# Mando.net
KiCad netlist of a schematic drawn in EAGLE
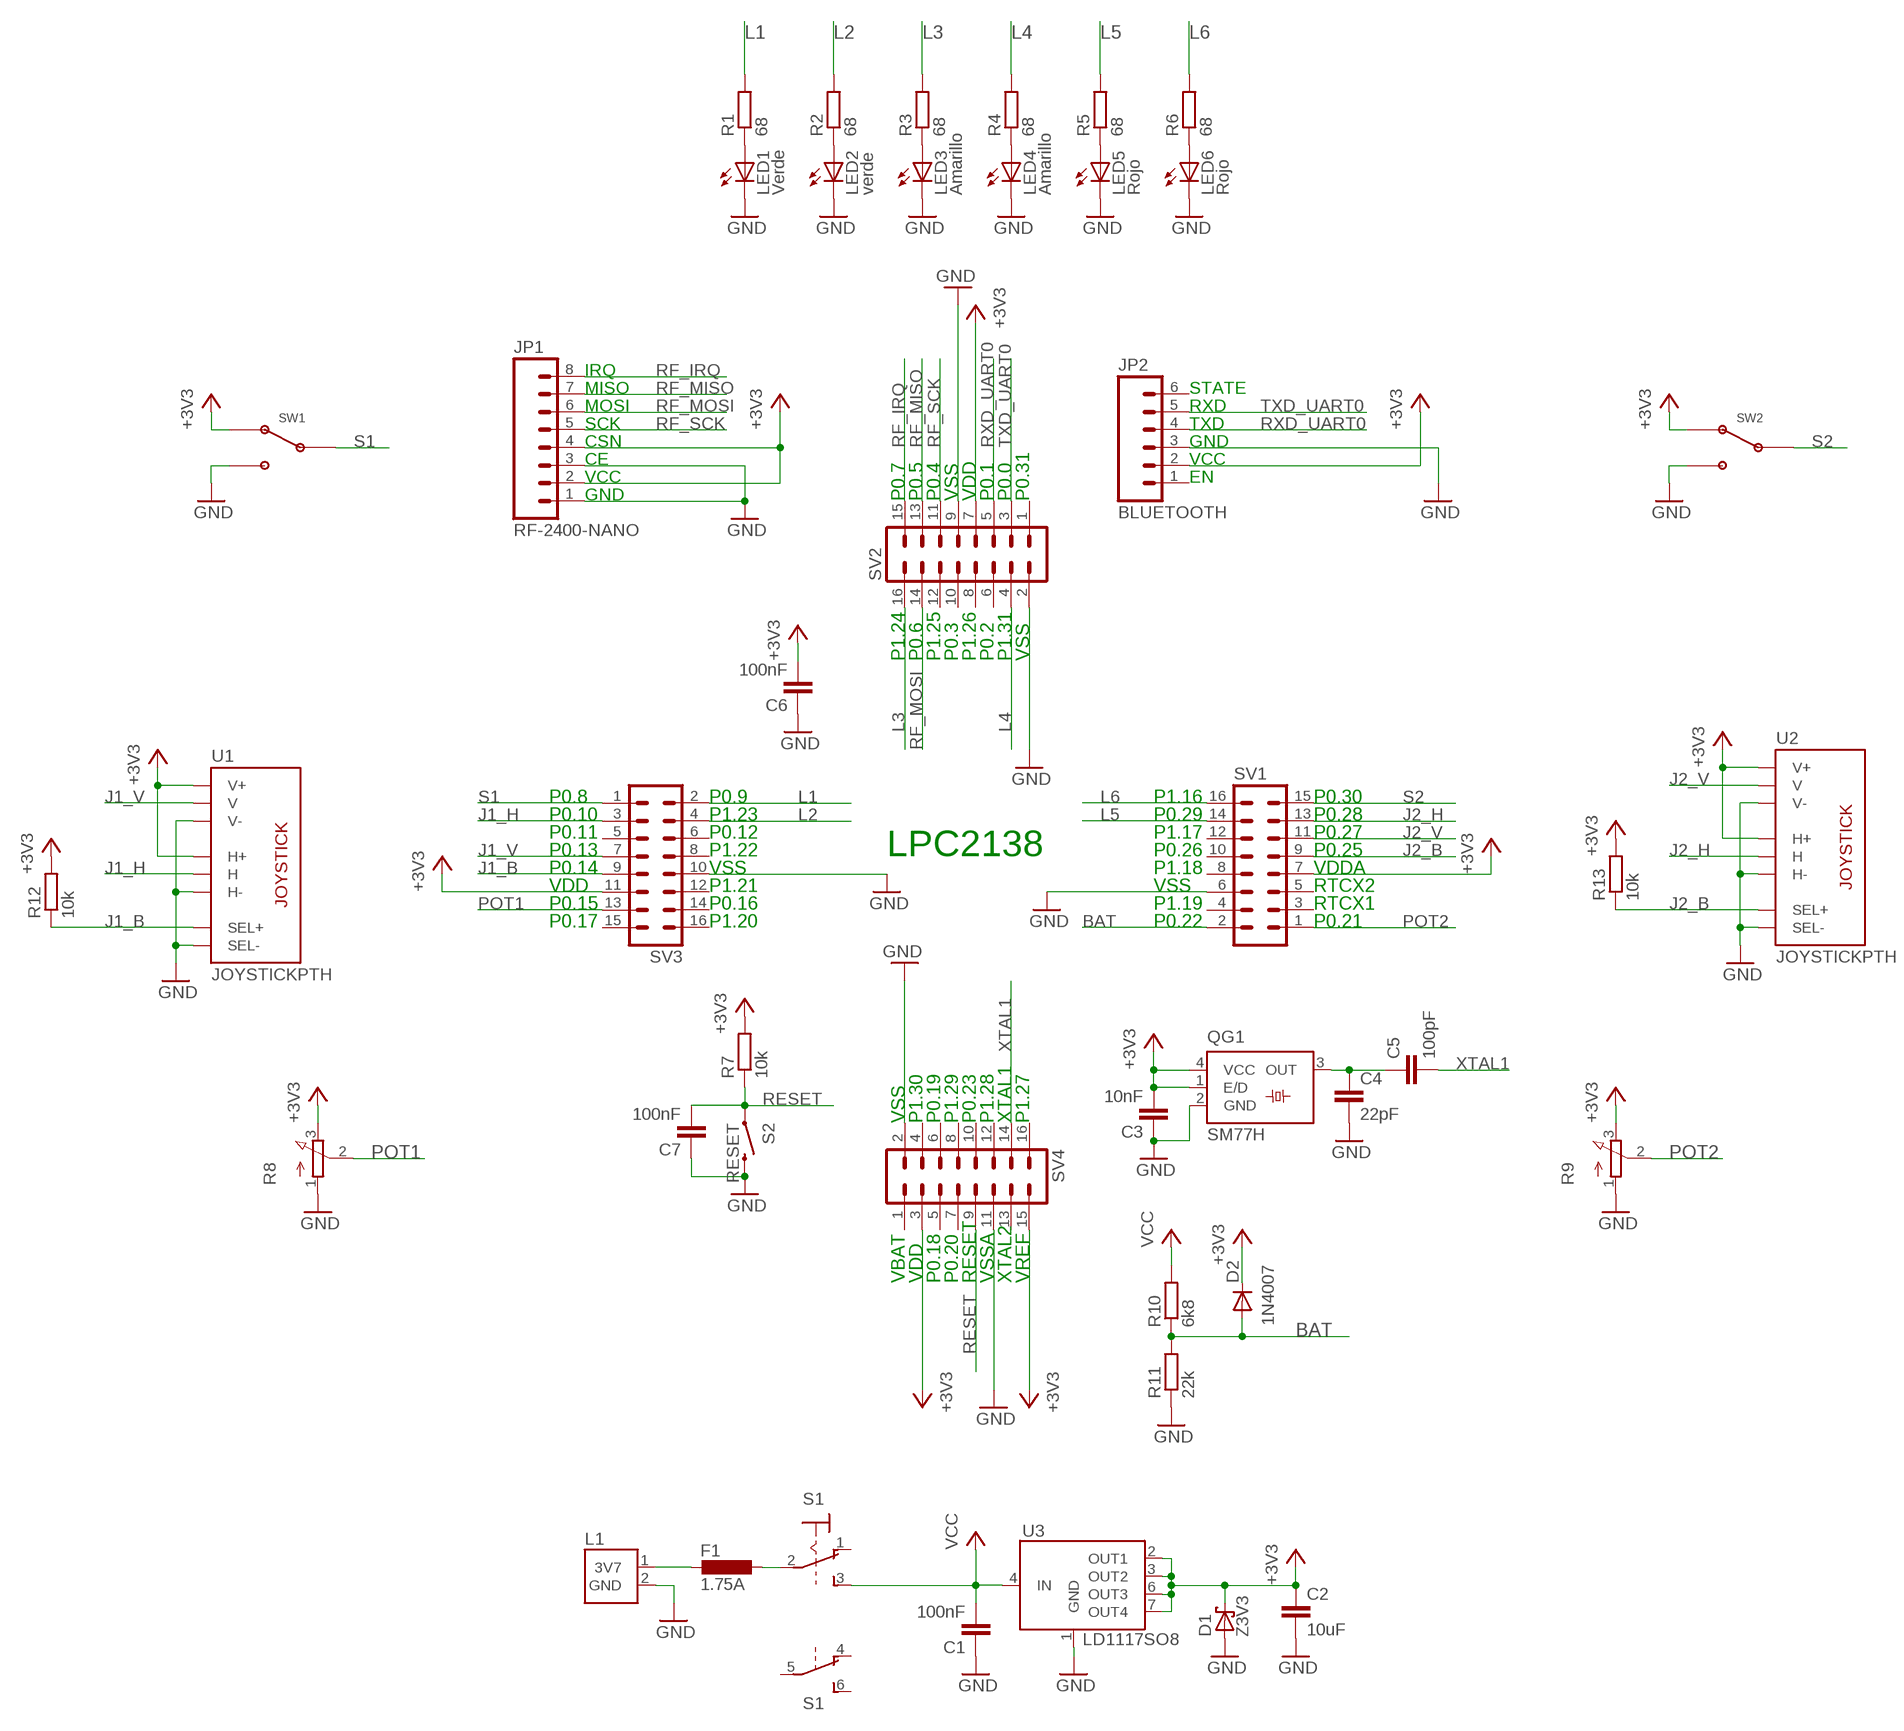
[diagram p0: schematic, sheet 1]

(export (version "E")
  (design (tool "Eeschema 10.0.6"))
  (components
    (comp (ref "C1")
      (value "100nF")
      (footprint "eagle-import:C0805")
      (libsource (lib "eagle-import") (part "C-EUC0805"))
    )
    (comp (ref "C2")
      (value "10uF")
      (footprint "eagle-import:C1206")
      (libsource (lib "eagle-import") (part "C-EUC1206"))
    )
    (comp (ref "C3")
      (value "10nF")
      (footprint "eagle-import:C0805")
      (libsource (lib "eagle-import") (part "C-EUC0805"))
    )
    (comp (ref "C4")
      (value "22pF")
      (footprint "eagle-import:C0805")
      (libsource (lib "eagle-import") (part "C-EUC0805"))
    )
    (comp (ref "C5")
      (value "100pF")
      (footprint "eagle-import:C0805")
      (libsource (lib "eagle-import") (part "C-EUC0805"))
    )
    (comp (ref "C6")
      (value "100nF")
      (footprint "eagle-import:C0805")
      (libsource (lib "eagle-import") (part "C-EUC0805"))
    )
    (comp (ref "C7")
      (value "100nF")
      (footprint "eagle-import:C0805")
      (libsource (lib "eagle-import") (part "C-EUC0805"))
    )
    (comp (ref "D1")
      (value "Z3V3")
      (footprint "eagle-import:DO35-7")
      (libsource (lib "eagle-import") (part "SCHOTTKY-DIODEDO35-7"))
    )
    (comp (ref "D2")
      (value "1N4007")
      (footprint "eagle-import:SOD106-R")
      (libsource (lib "eagle-import") (part "DIODE-SOD106-R"))
    )
    (comp (ref "F1")
      (value "1.75A")
      (footprint "eagle-import:L1812")
      (libsource (lib "eagle-import") (part "L-EUL1812"))
    )
    (comp (ref "JP1")
      (value "RF-2400-NANO")
      (footprint "eagle-import:1X08")
      (libsource (lib "eagle-import") (part "M081X08"))
    )
    (comp (ref "JP2")
      (value "BLUETOOTH")
      (footprint "eagle-import:1X06")
      (libsource (lib "eagle-import") (part "M06SIP"))
    )
    (comp (ref "L1")
      (value "CONECTOR_LIPO_3.7V")
      (footprint "eagle-import:CONECTOR_LIPO_3.7V")
      (libsource (lib "eagle-import") (part "CONECTOR_LIPO_3.7V"))
    )
    (comp (ref "LED1")
      (value "Verde")
      (footprint "eagle-import:LED3MM")
      (libsource (lib "eagle-import") (part "LED3MM"))
    )
    (comp (ref "LED2")
      (value "verde")
      (footprint "eagle-import:LED3MM")
      (libsource (lib "eagle-import") (part "LED3MM"))
    )
    (comp (ref "LED3")
      (value "Amarillo")
      (footprint "eagle-import:LED3MM")
      (libsource (lib "eagle-import") (part "LED3MM"))
    )
    (comp (ref "LED4")
      (value "Amarillo")
      (footprint "eagle-import:LED3MM")
      (libsource (lib "eagle-import") (part "LED3MM"))
    )
    (comp (ref "LED5")
      (value "Rojo")
      (footprint "eagle-import:LED3MM")
      (libsource (lib "eagle-import") (part "LED3MM"))
    )
    (comp (ref "LED6")
      (value "Rojo")
      (footprint "eagle-import:LED3MM")
      (libsource (lib "eagle-import") (part "LED3MM"))
    )
    (comp (ref "QG1")
      (value "SM77H")
      (footprint "eagle-import:SM77H")
      (libsource (lib "eagle-import") (part "SM77H"))
    )
    (comp (ref "R1")
      (value "68")
      (footprint "eagle-import:M0805")
      (libsource (lib "eagle-import") (part "R-EU_M0805"))
    )
    (comp (ref "R2")
      (value "68")
      (footprint "eagle-import:M0805")
      (libsource (lib "eagle-import") (part "R-EU_M0805"))
    )
    (comp (ref "R3")
      (value "68")
      (footprint "eagle-import:M0805")
      (libsource (lib "eagle-import") (part "R-EU_M0805"))
    )
    (comp (ref "R4")
      (value "68")
      (footprint "eagle-import:M0805")
      (libsource (lib "eagle-import") (part "R-EU_M0805"))
    )
    (comp (ref "R5")
      (value "68")
      (footprint "eagle-import:M0805")
      (libsource (lib "eagle-import") (part "R-EU_M0805"))
    )
    (comp (ref "R6")
      (value "68")
      (footprint "eagle-import:M0805")
      (libsource (lib "eagle-import") (part "R-EU_M0805"))
    )
    (comp (ref "R7")
      (value "10k")
      (footprint "eagle-import:M0805")
      (libsource (lib "eagle-import") (part "R-EU_M0805"))
    )
    (comp (ref "R8")
      (value "3RP/1610N")
      (footprint "eagle-import:3RP_1610N")
      (libsource (lib "eagle-import") (part "3RP/1610N"))
    )
    (comp (ref "R9")
      (value "3RP/1610N")
      (footprint "eagle-import:3RP_1610N")
      (libsource (lib "eagle-import") (part "3RP/1610N"))
    )
    (comp (ref "R10")
      (value "6k8")
      (footprint "eagle-import:M0805")
      (libsource (lib "eagle-import") (part "R-EU_M0805"))
    )
    (comp (ref "R11")
      (value "22k")
      (footprint "eagle-import:M0805")
      (libsource (lib "eagle-import") (part "R-EU_M0805"))
    )
    (comp (ref "R12")
      (value "10k")
      (footprint "eagle-import:M0805")
      (libsource (lib "eagle-import") (part "R-EU_M0805"))
    )
    (comp (ref "R13")
      (value "10k")
      (footprint "eagle-import:M0805")
      (libsource (lib "eagle-import") (part "R-EU_M0805"))
    )
    (comp (ref "S1")
      (value "SWITCH_2P2T_SL")
      (footprint "eagle-import:SLIDE_SWITCH_2P2T")
      (libsource (lib "eagle-import") (part "SWITCH_2P2T_SL"))
    )
    (comp (ref "S2")
      (value "RESET")
      (footprint "eagle-import:TACTILE-PTH")
      (libsource (lib "eagle-import") (part "SWITCH-MOMENTARY-2PTH"))
    )
    (comp (ref "SV1")
      (value "MA08-2")
      (footprint "eagle-import:MA08-2")
      (libsource (lib "eagle-import") (part "MA08-2"))
    )
    (comp (ref "SV2")
      (value "MA08-2")
      (footprint "eagle-import:MA08-2")
      (libsource (lib "eagle-import") (part "MA08-2"))
    )
    (comp (ref "SV3")
      (value "MA08-2")
      (footprint "eagle-import:MA08-2")
      (libsource (lib "eagle-import") (part "MA08-2"))
    )
    (comp (ref "SV4")
      (value "MA08-2")
      (footprint "eagle-import:MA08-2")
      (libsource (lib "eagle-import") (part "MA08-2"))
    )
    (comp (ref "SW1")
      (value "SW_1382_R/A")
      (footprint "eagle-import:SW_MX1382")
      (libsource (lib "eagle-import") (part "SW_1382_R/A"))
    )
    (comp (ref "SW2")
      (value "SW_1382_R/A")
      (footprint "eagle-import:SW_MX1382")
      (libsource (lib "eagle-import") (part "SW_1382_R/A"))
    )
    (comp (ref "U1")
      (value "JOYSTICKPTH")
      (footprint "eagle-import:JOYSTICK")
      (libsource (lib "eagle-import") (part "JOYSTICKPTH"))
    )
    (comp (ref "U2")
      (value "JOYSTICKPTH")
      (footprint "eagle-import:JOYSTICK")
      (libsource (lib "eagle-import") (part "JOYSTICKPTH"))
    )
    (comp (ref "U3")
      (value "LD1117SO8")
      (footprint "eagle-import:SO8")
      (libsource (lib "eagle-import") (part "LD1117SO8"))
    )
  )
  (nets
    (net (code "1") (name "+3V3") (class "Default")
      (node (ref "C2") (pin "1") (pinfunction "1_1") (pintype "passive"))
      (node (ref "C3") (pin "2") (pinfunction "2_2") (pintype "passive"))
      (node (ref "C6") (pin "2") (pinfunction "2_2") (pintype "passive"))
      (node (ref "D1") (pin "C") (pinfunction "C_C") (pintype "passive"))
      (node (ref "D2") (pin "C") (pinfunction "C_C") (pintype "passive"))
      (node (ref "JP1") (pin "2") (pinfunction "2_2") (pintype "passive"))
      (node (ref "JP1") (pin "4") (pinfunction "4_4") (pintype "passive"))
      (node (ref "JP2") (pin "2") (pinfunction "2_2") (pintype "passive"))
      (node (ref "QG1") (pin "1") (pinfunction "E/D_1") (pintype "input"))
      (node (ref "QG1") (pin "4") (pinfunction "VCC_4") (pintype "power_in"))
      (node (ref "R12") (pin "2") (pinfunction "2_2") (pintype "passive"))
      (node (ref "R13") (pin "2") (pinfunction "2_2") (pintype "passive"))
      (node (ref "R7") (pin "2") (pinfunction "2_2") (pintype "passive"))
      (node (ref "R8") (pin "3") (pinfunction "E_3") (pintype "passive"))
      (node (ref "R9") (pin "3") (pinfunction "E_3") (pintype "passive"))
      (node (ref "SV1") (pin "7") (pinfunction "7_7") (pintype "passive"))
      (node (ref "SV2") (pin "7") (pinfunction "7_7") (pintype "passive"))
      (node (ref "SV3") (pin "11") (pinfunction "11_11") (pintype "passive"))
      (node (ref "SV4") (pin "15") (pinfunction "15_15") (pintype "passive"))
      (node (ref "SV4") (pin "3") (pinfunction "3_3") (pintype "passive"))
      (node (ref "SW1") (pin "N.C") (pinfunction "N.C_N.C") (pintype "bidirectional"))
      (node (ref "SW2") (pin "N.C") (pinfunction "N.C_N.C") (pintype "bidirectional"))
      (node (ref "U1") (pin "H1") (pinfunction "H+_H1") (pintype "bidirectional"))
      (node (ref "U1") (pin "V1") (pinfunction "V+_V1") (pintype "bidirectional"))
      (node (ref "U2") (pin "H1") (pinfunction "H+_H1") (pintype "bidirectional"))
      (node (ref "U2") (pin "V1") (pinfunction "V+_V1") (pintype "bidirectional"))
      (node (ref "U3") (pin "2") (pinfunction "OUT1_2") (pintype "output"))
      (node (ref "U3") (pin "3") (pinfunction "OUT2_3") (pintype "output"))
      (node (ref "U3") (pin "6") (pinfunction "OUT3_6") (pintype "output"))
      (node (ref "U3") (pin "7") (pinfunction "OUT4_7") (pintype "output"))
    )
    (net (code "2") (name "/BAT") (class "Default")
      (node (ref "D2") (pin "A") (pinfunction "A_A") (pintype "passive"))
      (node (ref "R10") (pin "1") (pinfunction "1_1") (pintype "passive"))
      (node (ref "R11") (pin "2") (pinfunction "2_2") (pintype "passive"))
      (node (ref "SV1") (pin "2") (pinfunction "2_2") (pintype "passive"))
    )
    (net (code "3") (name "/J1_B") (class "Default")
      (node (ref "R12") (pin "1") (pinfunction "1_1") (pintype "passive"))
      (node (ref "SV3") (pin "9") (pinfunction "9_9") (pintype "passive"))
      (node (ref "U1") (pin "B1A") (pinfunction "SEL+_B1A") (pintype "bidirectional"))
    )
    (net (code "4") (name "/J1_H") (class "Default")
      (node (ref "SV3") (pin "3") (pinfunction "3_3") (pintype "passive"))
      (node (ref "U1") (pin "H2") (pinfunction "H_H2") (pintype "bidirectional"))
    )
    (net (code "5") (name "/J1_V") (class "Default")
      (node (ref "SV3") (pin "7") (pinfunction "7_7") (pintype "passive"))
      (node (ref "U1") (pin "V2") (pinfunction "V_V2") (pintype "bidirectional"))
    )
    (net (code "6") (name "/J2_B") (class "Default")
      (node (ref "R13") (pin "1") (pinfunction "1_1") (pintype "passive"))
      (node (ref "SV1") (pin "9") (pinfunction "9_9") (pintype "passive"))
      (node (ref "U2") (pin "B1A") (pinfunction "SEL+_B1A") (pintype "bidirectional"))
    )
    (net (code "7") (name "/J2_H") (class "Default")
      (node (ref "SV1") (pin "13") (pinfunction "13_13") (pintype "passive"))
      (node (ref "U2") (pin "H2") (pinfunction "H_H2") (pintype "bidirectional"))
    )
    (net (code "8") (name "/J2_V") (class "Default")
      (node (ref "SV1") (pin "11") (pinfunction "11_11") (pintype "passive"))
      (node (ref "U2") (pin "V2") (pinfunction "V_V2") (pintype "bidirectional"))
    )
    (net (code "9") (name "/L1") (class "Default")
      (node (ref "R1") (pin "2") (pinfunction "2_2") (pintype "passive"))
      (node (ref "SV3") (pin "2") (pinfunction "2_2") (pintype "passive"))
    )
    (net (code "10") (name "/L2") (class "Default")
      (node (ref "R2") (pin "2") (pinfunction "2_2") (pintype "passive"))
      (node (ref "SV3") (pin "4") (pinfunction "4_4") (pintype "passive"))
    )
    (net (code "11") (name "/L3") (class "Default")
      (node (ref "R3") (pin "2") (pinfunction "2_2") (pintype "passive"))
      (node (ref "SV2") (pin "16") (pinfunction "16_16") (pintype "passive"))
    )
    (net (code "12") (name "/L4") (class "Default")
      (node (ref "R4") (pin "2") (pinfunction "2_2") (pintype "passive"))
      (node (ref "SV2") (pin "4") (pinfunction "4_4") (pintype "passive"))
    )
    (net (code "13") (name "/L5") (class "Default")
      (node (ref "R5") (pin "2") (pinfunction "2_2") (pintype "passive"))
      (node (ref "SV1") (pin "14") (pinfunction "14_14") (pintype "passive"))
    )
    (net (code "14") (name "/L6") (class "Default")
      (node (ref "R6") (pin "2") (pinfunction "2_2") (pintype "passive"))
      (node (ref "SV1") (pin "16") (pinfunction "16_16") (pintype "passive"))
    )
    (net (code "15") (name "/POT1") (class "Default")
      (node (ref "R8") (pin "2") (pinfunction "S_2") (pintype "passive"))
      (node (ref "SV3") (pin "13") (pinfunction "13_13") (pintype "passive"))
    )
    (net (code "16") (name "/POT2") (class "Default")
      (node (ref "R9") (pin "2") (pinfunction "S_2") (pintype "passive"))
      (node (ref "SV1") (pin "1") (pinfunction "1_1") (pintype "passive"))
    )
    (net (code "17") (name "/RESET") (class "Default")
      (node (ref "C7") (pin "2") (pinfunction "2_2") (pintype "passive"))
      (node (ref "R7") (pin "1") (pinfunction "1_1") (pintype "passive"))
      (node (ref "S2") (pin "1") (pinfunction "1_1") (pintype "passive"))
      (node (ref "SV4") (pin "9") (pinfunction "9_9") (pintype "passive"))
    )
    (net (code "18") (name "/RF_IRQ") (class "Default")
      (node (ref "JP1") (pin "8") (pinfunction "8_8") (pintype "passive"))
      (node (ref "SV2") (pin "15") (pinfunction "15_15") (pintype "passive"))
    )
    (net (code "19") (name "/RF_MISO") (class "Default")
      (node (ref "JP1") (pin "7") (pinfunction "7_7") (pintype "passive"))
      (node (ref "SV2") (pin "13") (pinfunction "13_13") (pintype "passive"))
    )
    (net (code "20") (name "/RF_MOSI") (class "Default")
      (node (ref "JP1") (pin "6") (pinfunction "6_6") (pintype "passive"))
      (node (ref "SV2") (pin "14") (pinfunction "14_14") (pintype "passive"))
    )
    (net (code "21") (name "/RF_SCK") (class "Default")
      (node (ref "JP1") (pin "5") (pinfunction "5_5") (pintype "passive"))
      (node (ref "SV2") (pin "11") (pinfunction "11_11") (pintype "passive"))
    )
    (net (code "22") (name "/RXD_UART0") (class "Default")
      (node (ref "JP2") (pin "4") (pinfunction "4_4") (pintype "passive"))
      (node (ref "SV2") (pin "5") (pinfunction "5_5") (pintype "passive"))
    )
    (net (code "23") (name "/S1") (class "Default")
      (node (ref "SV3") (pin "1") (pinfunction "1_1") (pintype "passive"))
      (node (ref "SW1") (pin "COM") (pinfunction "COM_COM") (pintype "bidirectional"))
    )
    (net (code "24") (name "/S2") (class "Default")
      (node (ref "SV1") (pin "15") (pinfunction "15_15") (pintype "passive"))
      (node (ref "SW2") (pin "COM") (pinfunction "COM_COM") (pintype "bidirectional"))
    )
    (net (code "25") (name "/TXD_UART0") (class "Default")
      (node (ref "JP2") (pin "5") (pinfunction "5_5") (pintype "passive"))
      (node (ref "SV2") (pin "3") (pinfunction "3_3") (pintype "passive"))
    )
    (net (code "26") (name "/XTAL1") (class "Default")
      (node (ref "C5") (pin "2") (pinfunction "2_2") (pintype "passive"))
      (node (ref "SV4") (pin "14") (pinfunction "14_14") (pintype "passive"))
    )
    (net (code "27") (name "GND") (class "Default")
      (node (ref "C1") (pin "1") (pinfunction "1_1") (pintype "passive"))
      (node (ref "C2") (pin "2") (pinfunction "2_2") (pintype "passive"))
      (node (ref "C3") (pin "1") (pinfunction "1_1") (pintype "passive"))
      (node (ref "C4") (pin "2") (pinfunction "2_2") (pintype "passive"))
      (node (ref "C6") (pin "1") (pinfunction "1_1") (pintype "passive"))
      (node (ref "C7") (pin "1") (pinfunction "1_1") (pintype "passive"))
      (node (ref "D1") (pin "A") (pinfunction "A_A") (pintype "passive"))
      (node (ref "JP1") (pin "1") (pinfunction "1_1") (pintype "passive"))
      (node (ref "JP1") (pin "3") (pinfunction "3_3") (pintype "passive"))
      (node (ref "JP2") (pin "3") (pinfunction "3_3") (pintype "passive"))
      (node (ref "L1") (pin "2") (pinfunction "GND_2") (pintype "power_in"))
      (node (ref "LED1") (pin "K") (pinfunction "C_K") (pintype "passive"))
      (node (ref "LED2") (pin "K") (pinfunction "C_K") (pintype "passive"))
      (node (ref "LED3") (pin "K") (pinfunction "C_K") (pintype "passive"))
      (node (ref "LED4") (pin "K") (pinfunction "C_K") (pintype "passive"))
      (node (ref "LED5") (pin "K") (pinfunction "C_K") (pintype "passive"))
      (node (ref "LED6") (pin "K") (pinfunction "C_K") (pintype "passive"))
      (node (ref "QG1") (pin "2") (pinfunction "GND_2") (pintype "power_in"))
      (node (ref "R11") (pin "1") (pinfunction "1_1") (pintype "passive"))
      (node (ref "R8") (pin "1") (pinfunction "A_1") (pintype "passive"))
      (node (ref "R9") (pin "1") (pinfunction "A_1") (pintype "passive"))
      (node (ref "S2") (pin "3") (pinfunction "2_3") (pintype "passive"))
      (node (ref "SV1") (pin "6") (pinfunction "6_6") (pintype "passive"))
      (node (ref "SV2") (pin "2") (pinfunction "2_2") (pintype "passive"))
      (node (ref "SV2") (pin "9") (pinfunction "9_9") (pintype "passive"))
      (node (ref "SV3") (pin "10") (pinfunction "10_10") (pintype "passive"))
      (node (ref "SV4") (pin "11") (pinfunction "11_11") (pintype "passive"))
      (node (ref "SV4") (pin "2") (pinfunction "2_2") (pintype "passive"))
      (node (ref "SW1") (pin "N.O") (pinfunction "N.O_N.O") (pintype "bidirectional"))
      (node (ref "SW2") (pin "N.O") (pinfunction "N.O_N.O") (pintype "bidirectional"))
      (node (ref "U1") (pin "B2A") (pinfunction "SEL-_B2A") (pintype "bidirectional"))
      (node (ref "U1") (pin "H3") (pinfunction "H-_H3") (pintype "bidirectional"))
      (node (ref "U1") (pin "V3") (pinfunction "V-_V3") (pintype "bidirectional"))
      (node (ref "U2") (pin "B2A") (pinfunction "SEL-_B2A") (pintype "bidirectional"))
      (node (ref "U2") (pin "H3") (pinfunction "H-_H3") (pintype "bidirectional"))
      (node (ref "U2") (pin "V3") (pinfunction "V-_V3") (pintype "bidirectional"))
      (node (ref "U3") (pin "1") (pinfunction "GND_1") (pintype "power_in"))
    )
    (net (code "28") (name "Net-(L1-3V7)") (class "Default")
      (node (ref "F1") (pin "2") (pinfunction "2_2") (pintype "passive"))
      (node (ref "L1") (pin "1") (pinfunction "3V7_1") (pintype "power_in"))
    )
    (net (code "29") (name "Net-(LED1-PadA)") (class "Default")
      (node (ref "LED1") (pin "A") (pinfunction "A_A") (pintype "passive"))
      (node (ref "R1") (pin "1") (pinfunction "1_1") (pintype "passive"))
    )
    (net (code "30") (name "Net-(LED2-PadA)") (class "Default")
      (node (ref "LED2") (pin "A") (pinfunction "A_A") (pintype "passive"))
      (node (ref "R2") (pin "1") (pinfunction "1_1") (pintype "passive"))
    )
    (net (code "31") (name "Net-(LED3-PadA)") (class "Default")
      (node (ref "LED3") (pin "A") (pinfunction "A_A") (pintype "passive"))
      (node (ref "R3") (pin "1") (pinfunction "1_1") (pintype "passive"))
    )
    (net (code "32") (name "Net-(LED4-PadA)") (class "Default")
      (node (ref "LED4") (pin "A") (pinfunction "A_A") (pintype "passive"))
      (node (ref "R4") (pin "1") (pinfunction "1_1") (pintype "passive"))
    )
    (net (code "33") (name "Net-(LED5-PadA)") (class "Default")
      (node (ref "LED5") (pin "A") (pinfunction "A_A") (pintype "passive"))
      (node (ref "R5") (pin "1") (pinfunction "1_1") (pintype "passive"))
    )
    (net (code "34") (name "Net-(LED6-PadA)") (class "Default")
      (node (ref "LED6") (pin "A") (pinfunction "A_A") (pintype "passive"))
      (node (ref "R6") (pin "1") (pinfunction "1_1") (pintype "passive"))
    )
    (net (code "35") (name "Net-(QG1-OUT)") (class "Default")
      (node (ref "C4") (pin "1") (pinfunction "1_1") (pintype "passive"))
      (node (ref "C5") (pin "1") (pinfunction "1_1") (pintype "passive"))
      (node (ref "QG1") (pin "3") (pinfunction "OUT_3") (pintype "output"))
    )
    (net (code "36") (name "Net-(S1A-P)") (class "Default")
      (node (ref "F1") (pin "1") (pinfunction "1_1") (pintype "passive"))
      (node (ref "S1") (pin "2") (pinfunction "P_2") (pintype "passive"))
    )
    (net (code "37") (name "VCC") (class "Default")
      (node (ref "C1") (pin "2") (pinfunction "2_2") (pintype "passive"))
      (node (ref "R10") (pin "2") (pinfunction "2_2") (pintype "passive"))
      (node (ref "S1") (pin "3") (pinfunction "S_3") (pintype "passive"))
      (node (ref "U3") (pin "4") (pinfunction "IN_4") (pintype "power_in"))
    )
    (net (code "38") (name "unconnected-(JP2-Pad1)") (class "Default")
      (node (ref "JP2") (pin "1") (pinfunction "1_1") (pintype "passive"))
    )
    (net (code "39") (name "unconnected-(JP2-Pad6)") (class "Default")
      (node (ref "JP2") (pin "6") (pinfunction "6_6") (pintype "passive"))
    )
    (net (code "40") (name "unconnected-(S1A-O-Pad1)") (class "Default")
      (node (ref "S1") (pin "1") (pinfunction "O_1") (pintype "passive"))
    )
    (net (code "41") (name "unconnected-(S1B-O-Pad4)") (class "Default")
      (node (ref "S1") (pin "4") (pinfunction "O_4") (pintype "passive"))
    )
    (net (code "42") (name "unconnected-(S1B-P-Pad5)") (class "Default")
      (node (ref "S1") (pin "5") (pinfunction "P_5") (pintype "passive"))
    )
    (net (code "43") (name "unconnected-(S1B-S-Pad6)") (class "Default")
      (node (ref "S1") (pin "6") (pinfunction "S_6") (pintype "passive"))
    )
    (net (code "44") (name "unconnected-(SV1-Pad3)") (class "Default")
      (node (ref "SV1") (pin "3") (pinfunction "3_3") (pintype "passive"))
    )
    (net (code "45") (name "unconnected-(SV1-Pad4)") (class "Default")
      (node (ref "SV1") (pin "4") (pinfunction "4_4") (pintype "passive"))
    )
    (net (code "46") (name "unconnected-(SV1-Pad5)") (class "Default")
      (node (ref "SV1") (pin "5") (pinfunction "5_5") (pintype "passive"))
    )
    (net (code "47") (name "unconnected-(SV1-Pad8)") (class "Default")
      (node (ref "SV1") (pin "8") (pinfunction "8_8") (pintype "passive"))
    )
    (net (code "48") (name "unconnected-(SV1-Pad10)") (class "Default")
      (node (ref "SV1") (pin "10") (pinfunction "10_10") (pintype "passive"))
    )
    (net (code "49") (name "unconnected-(SV1-Pad12)") (class "Default")
      (node (ref "SV1") (pin "12") (pinfunction "12_12") (pintype "passive"))
    )
    (net (code "50") (name "unconnected-(SV2-Pad1)") (class "Default")
      (node (ref "SV2") (pin "1") (pinfunction "1_1") (pintype "passive"))
    )
    (net (code "51") (name "unconnected-(SV2-Pad6)") (class "Default")
      (node (ref "SV2") (pin "6") (pinfunction "6_6") (pintype "passive"))
    )
    (net (code "52") (name "unconnected-(SV2-Pad8)") (class "Default")
      (node (ref "SV2") (pin "8") (pinfunction "8_8") (pintype "passive"))
    )
    (net (code "53") (name "unconnected-(SV2-Pad10)") (class "Default")
      (node (ref "SV2") (pin "10") (pinfunction "10_10") (pintype "passive"))
    )
    (net (code "54") (name "unconnected-(SV2-Pad12)") (class "Default")
      (node (ref "SV2") (pin "12") (pinfunction "12_12") (pintype "passive"))
    )
    (net (code "55") (name "unconnected-(SV3-Pad5)") (class "Default")
      (node (ref "SV3") (pin "5") (pinfunction "5_5") (pintype "passive"))
    )
    (net (code "56") (name "unconnected-(SV3-Pad6)") (class "Default")
      (node (ref "SV3") (pin "6") (pinfunction "6_6") (pintype "passive"))
    )
    (net (code "57") (name "unconnected-(SV3-Pad8)") (class "Default")
      (node (ref "SV3") (pin "8") (pinfunction "8_8") (pintype "passive"))
    )
    (net (code "58") (name "unconnected-(SV3-Pad12)") (class "Default")
      (node (ref "SV3") (pin "12") (pinfunction "12_12") (pintype "passive"))
    )
    (net (code "59") (name "unconnected-(SV3-Pad14)") (class "Default")
      (node (ref "SV3") (pin "14") (pinfunction "14_14") (pintype "passive"))
    )
    (net (code "60") (name "unconnected-(SV3-Pad15)") (class "Default")
      (node (ref "SV3") (pin "15") (pinfunction "15_15") (pintype "passive"))
    )
    (net (code "61") (name "unconnected-(SV3-Pad16)") (class "Default")
      (node (ref "SV3") (pin "16") (pinfunction "16_16") (pintype "passive"))
    )
    (net (code "62") (name "unconnected-(SV4-Pad1)") (class "Default")
      (node (ref "SV4") (pin "1") (pinfunction "1_1") (pintype "passive"))
    )
    (net (code "63") (name "unconnected-(SV4-Pad4)") (class "Default")
      (node (ref "SV4") (pin "4") (pinfunction "4_4") (pintype "passive"))
    )
    (net (code "64") (name "unconnected-(SV4-Pad5)") (class "Default")
      (node (ref "SV4") (pin "5") (pinfunction "5_5") (pintype "passive"))
    )
    (net (code "65") (name "unconnected-(SV4-Pad6)") (class "Default")
      (node (ref "SV4") (pin "6") (pinfunction "6_6") (pintype "passive"))
    )
    (net (code "66") (name "unconnected-(SV4-Pad7)") (class "Default")
      (node (ref "SV4") (pin "7") (pinfunction "7_7") (pintype "passive"))
    )
    (net (code "67") (name "unconnected-(SV4-Pad8)") (class "Default")
      (node (ref "SV4") (pin "8") (pinfunction "8_8") (pintype "passive"))
    )
    (net (code "68") (name "unconnected-(SV4-Pad10)") (class "Default")
      (node (ref "SV4") (pin "10") (pinfunction "10_10") (pintype "passive"))
    )
    (net (code "69") (name "unconnected-(SV4-Pad12)") (class "Default")
      (node (ref "SV4") (pin "12") (pinfunction "12_12") (pintype "passive"))
    )
    (net (code "70") (name "unconnected-(SV4-Pad13)") (class "Default")
      (node (ref "SV4") (pin "13") (pinfunction "13_13") (pintype "passive"))
    )
    (net (code "71") (name "unconnected-(SV4-Pad16)") (class "Default")
      (node (ref "SV4") (pin "16") (pinfunction "16_16") (pintype "passive"))
    )
  )
)
